# si4012_RTTY_01.net
KiCad netlist of a schematic drawn in EAGLE
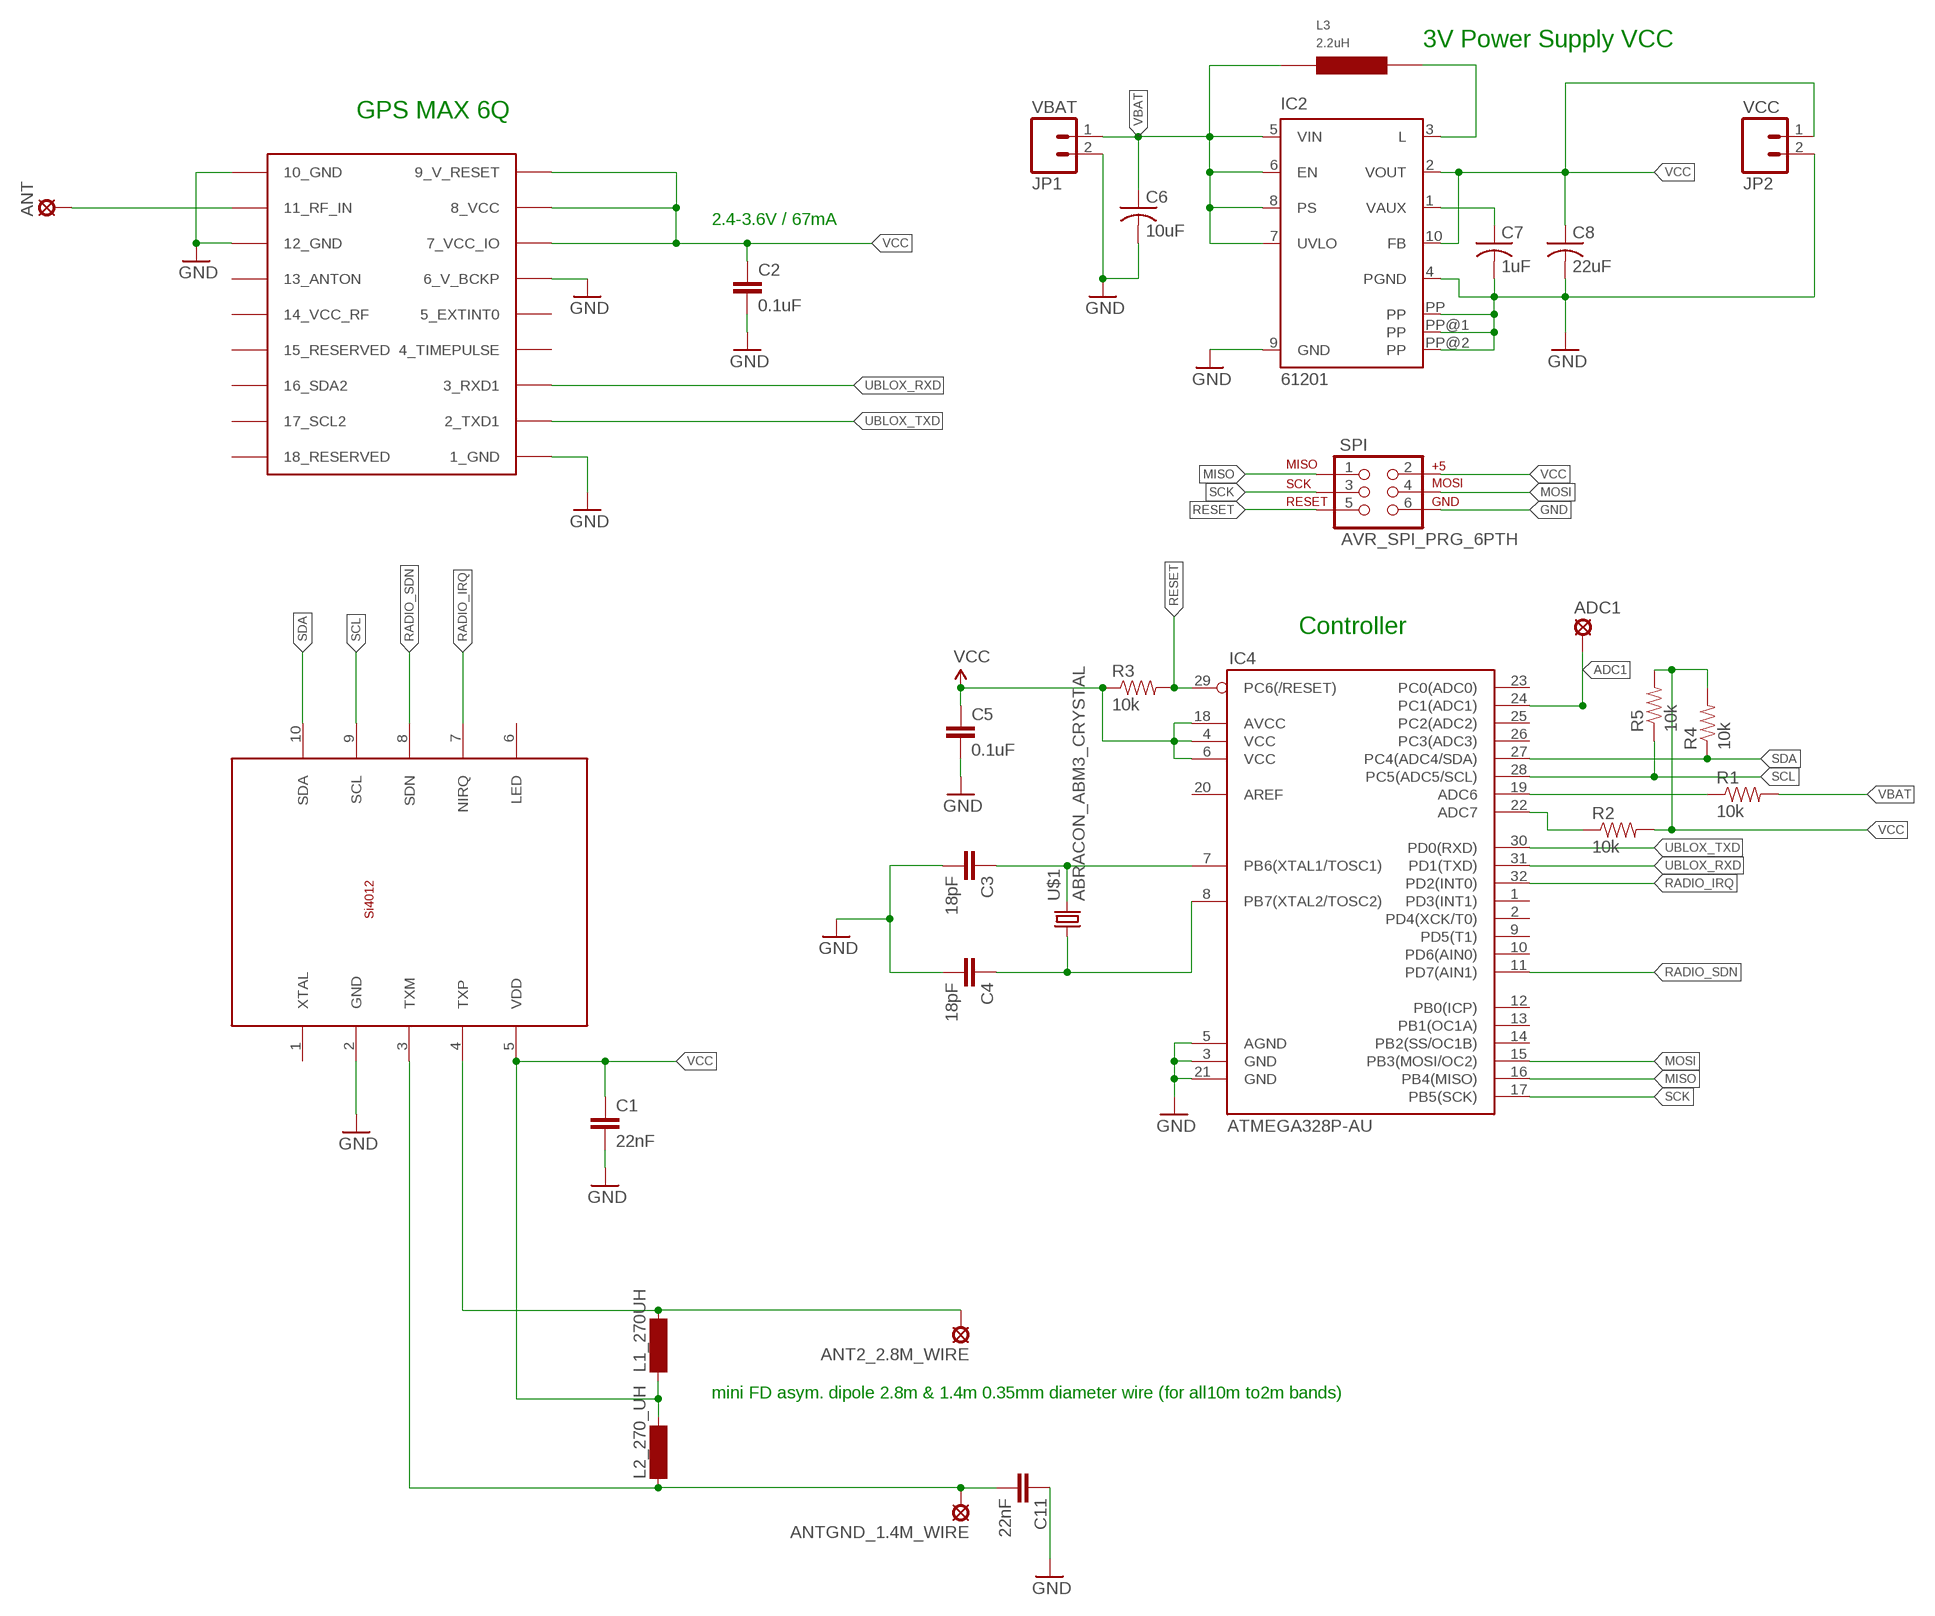
[diagram p0: schematic, sheet 1]

(export (version "E")
  (design (tool "Eeschema 10.0.6"))
  (components
    (comp (ref "ADC1")
      (value "LSP10")
      (footprint "eagle-import:LSP10")
      (libsource (lib "eagle-import") (part "LSP10"))
    )
    (comp (ref "ANT")
      (value "LSP10")
      (footprint "eagle-import:LSP10")
      (libsource (lib "eagle-import") (part "LSP10"))
    )
    (comp (ref "ANT2_2.8M_WIRE")
      (value "LSP10")
      (footprint "eagle-import:LSP10")
      (libsource (lib "eagle-import") (part "LSP10"))
    )
    (comp (ref "ANTGND_1.4M_WIRE")
      (value "LSP10")
      (footprint "eagle-import:LSP10")
      (libsource (lib "eagle-import") (part "LSP10"))
    )
    (comp (ref "C1")
      (value "22nF")
      (footprint "eagle-import:0402-CAP")
      (libsource (lib "eagle-import") (part "CAP0402-CAP"))
    )
    (comp (ref "C2")
      (value "0.1uF")
      (footprint "eagle-import:0402-CAP")
      (libsource (lib "eagle-import") (part "CAP0402-CAP"))
    )
    (comp (ref "C3")
      (value "18pF")
      (footprint "eagle-import:0402-CAP")
      (libsource (lib "eagle-import") (part "CAP0402-CAP"))
    )
    (comp (ref "C4")
      (value "18pF")
      (footprint "eagle-import:0402-CAP")
      (libsource (lib "eagle-import") (part "CAP0402-CAP"))
    )
    (comp (ref "C5")
      (value "0.1uF")
      (footprint "eagle-import:0402-CAP")
      (libsource (lib "eagle-import") (part "CAP0402-CAP"))
    )
    (comp (ref "C6")
      (value "10uF")
      (footprint "eagle-import:C1206")
      (libsource (lib "eagle-import") (part "C-USC1206"))
    )
    (comp (ref "C7")
      (value "1uF")
      (footprint "eagle-import:C1206")
      (libsource (lib "eagle-import") (part "C-USC1206"))
    )
    (comp (ref "C8")
      (value "22uF")
      (footprint "eagle-import:C1206")
      (libsource (lib "eagle-import") (part "C-USC1206"))
    )
    (comp (ref "C11")
      (value "22nF")
      (footprint "eagle-import:0402-CAP")
      (libsource (lib "eagle-import") (part "CAP0402-CAP"))
    )
    (comp (ref "IC2")
      (value "61201")
      (footprint "eagle-import:S-PDSO-N10")
      (fields (field (name "MPN") "TPS61201DRCT"))
      (libsource (lib "eagle-import") (part "TPS61201"))
    )
    (comp (ref "IC4")
      (value "ATMEGA328P-AU")
      (footprint "eagle-import:TQFP32-08")
      (libsource (lib "eagle-import") (part "ATMEGA168"))
    )
    (comp (ref "IC5")
      (value "UBLOX_MAX-6")
      (footprint "eagle-import:UBLOX_MAX-6")
      (libsource (lib "eagle-import") (part "UBLOX_MAX-6"))
    )
    (comp (ref "JP1")
      (value "VBAT")
      (footprint "eagle-import:1X02")
      (libsource (lib "eagle-import") (part "M02PTH"))
    )
    (comp (ref "JP2")
      (value "VCC")
      (footprint "eagle-import:1X02")
      (libsource (lib "eagle-import") (part "M02PTH"))
    )
    (comp (ref "L1_270UH")
      (value "SM-1206")
      (footprint "eagle-import:SM-1206")
      (libsource (lib "eagle-import") (part "SM-1206"))
    )
    (comp (ref "L2_270_UH")
      (value "SM-1206")
      (footprint "eagle-import:SM-1206")
      (libsource (lib "eagle-import") (part "SM-1206"))
    )
    (comp (ref "L3")
      (value "2.2uH")
      (footprint "eagle-import:LPS3015")
      (libsource (lib "eagle-import") (part "LPS3015"))
    )
    (comp (ref "R1")
      (value "10k")
      (footprint "eagle-import:0402-RES")
      (libsource (lib "eagle-import") (part "RESISTOR0402-RES"))
    )
    (comp (ref "R2")
      (value "10k")
      (footprint "eagle-import:0402-RES")
      (libsource (lib "eagle-import") (part "RESISTOR0402-RES"))
    )
    (comp (ref "R3")
      (value "10k")
      (footprint "eagle-import:0402-RES")
      (libsource (lib "eagle-import") (part "RESISTOR0402-RES"))
    )
    (comp (ref "R4")
      (value "10k")
      (footprint "eagle-import:0402-RES")
      (libsource (lib "eagle-import") (part "RESISTOR0402-RES"))
    )
    (comp (ref "R5")
      (value "10k")
      (footprint "eagle-import:0402-RES")
      (libsource (lib "eagle-import") (part "RESISTOR0402-RES"))
    )
    (comp (ref "SPI")
      (value "AVR_SPI_PRG_6PTH")
      (footprint "eagle-import:2X3")
      (libsource (lib "eagle-import") (part "AVR_SPI_PRG_6PTH"))
    )
    (comp (ref "U$1")
      (value "ABRACON_ABM3_CRYSTAL")
      (footprint "eagle-import:ABRACON_ABM3_CRYSTAL")
      (libsource (lib "eagle-import") (part "ABRACON_ABM3_CRYSTAL"))
    )
    (comp (ref "U$2")
      (value "SI4012")
      (footprint "eagle-import:MSOP_10")
      (libsource (lib "eagle-import") (part "SI4012"))
    )
  )
  (nets
    (net (code "1") (name "ADC1") (class "Default")
      (node (ref "ADC1") (pin "MP") (pinfunction "MP_MP") (pintype "passive"))
      (node (ref "IC4") (pin "24") (pinfunction "PC1(ADC1)_24") (pintype "bidirectional"))
    )
    (net (code "2") (name "GND") (class "Default")
      (node (ref "C1") (pin "2") (pinfunction "2_2") (pintype "passive"))
      (node (ref "C11") (pin "1") (pinfunction "1_1") (pintype "passive"))
      (node (ref "C2") (pin "2") (pinfunction "2_2") (pintype "passive"))
      (node (ref "C3") (pin "2") (pinfunction "2_2") (pintype "passive"))
      (node (ref "C4") (pin "2") (pinfunction "2_2") (pintype "passive"))
      (node (ref "C5") (pin "2") (pinfunction "2_2") (pintype "passive"))
      (node (ref "C6") (pin "2") (pinfunction "2_2") (pintype "passive"))
      (node (ref "C7") (pin "2") (pinfunction "2_2") (pintype "passive"))
      (node (ref "C8") (pin "2") (pinfunction "2_2") (pintype "passive"))
      (node (ref "IC2") (pin "4") (pinfunction "PGND_4") (pintype "power_in"))
      (node (ref "IC2") (pin "9") (pinfunction "GND_9") (pintype "power_in"))
      (node (ref "IC2") (pin "PP") (pinfunction "PP_PP") (pintype "power_in"))
      (node (ref "IC2") (pin "PP@1") (pinfunction "PP_PP@1") (pintype "power_in"))
      (node (ref "IC2") (pin "PP@2") (pinfunction "PP_PP@2") (pintype "power_in"))
      (node (ref "IC4") (pin "21") (pinfunction "GND_21") (pintype "bidirectional"))
      (node (ref "IC4") (pin "3") (pinfunction "GND_3") (pintype "bidirectional"))
      (node (ref "IC4") (pin "5") (pinfunction "AGND_5") (pintype "bidirectional"))
      (node (ref "IC5") (pin "10_GND") (pinfunction "10_GND_10_GND") (pintype "power_in"))
      (node (ref "IC5") (pin "12_GND") (pinfunction "12_GND_12_GND") (pintype "power_in"))
      (node (ref "IC5") (pin "1_GND") (pinfunction "1_GND_1_GND") (pintype "power_in"))
      (node (ref "IC5") (pin "6_V_BCKP") (pinfunction "6_V_BCKP_6_V_BCKP") (pintype "bidirectional"))
      (node (ref "JP1") (pin "2") (pinfunction "2_2") (pintype "passive"))
      (node (ref "JP2") (pin "2") (pinfunction "2_2") (pintype "passive"))
      (node (ref "SPI") (pin "6") (pinfunction "6_6") (pintype "passive"))
      (node (ref "U$2") (pin "2") (pinfunction "GND_2") (pintype "bidirectional"))
    )
    (net (code "3") (name "MISO") (class "Default")
      (node (ref "IC4") (pin "16") (pinfunction "PB4(MISO)_16") (pintype "bidirectional"))
      (node (ref "SPI") (pin "1") (pinfunction "1_1") (pintype "passive"))
    )
    (net (code "4") (name "MOSI") (class "Default")
      (node (ref "IC4") (pin "15") (pinfunction "PB3(MOSI/OC2)_15") (pintype "bidirectional"))
      (node (ref "SPI") (pin "4") (pinfunction "4_4") (pintype "passive"))
    )
    (net (code "5") (name "Net-(ANT-PadMP)") (class "Default")
      (node (ref "ANT") (pin "MP") (pinfunction "MP_MP") (pintype "passive"))
      (node (ref "IC5") (pin "11_RF_IN") (pinfunction "11_RF_IN_11_RF_IN") (pintype "bidirectional"))
    )
    (net (code "6") (name "Net-(IC2-L)") (class "Default")
      (node (ref "IC2") (pin "3") (pinfunction "L_3") (pintype "input"))
      (node (ref "L3") (pin "P$2") (pinfunction "2_P$2") (pintype "bidirectional"))
    )
    (net (code "7") (name "Net-(IC2-VAUX)") (class "Default")
      (node (ref "C7") (pin "1") (pinfunction "1_1") (pintype "passive"))
      (node (ref "IC2") (pin "1") (pinfunction "VAUX_1") (pintype "bidirectional"))
    )
    (net (code "8") (name "Net-(IC4-ADC6)") (class "Default")
      (node (ref "IC4") (pin "19") (pinfunction "ADC6_19") (pintype "bidirectional"))
      (node (ref "R1") (pin "1") (pinfunction "1_1") (pintype "passive"))
    )
    (net (code "9") (name "Net-(IC4-ADC7)") (class "Default")
      (node (ref "IC4") (pin "22") (pinfunction "ADC7_22") (pintype "bidirectional"))
      (node (ref "R2") (pin "1") (pinfunction "1_1") (pintype "passive"))
    )
    (net (code "10") (name "Net-(IC4-PB6(XTAL1{slash}TOSC1))") (class "Default")
      (node (ref "C3") (pin "1") (pinfunction "1_1") (pintype "passive"))
      (node (ref "IC4") (pin "7") (pinfunction "PB6(XTAL1/TOSC1)_7") (pintype "bidirectional"))
      (node (ref "U$1") (pin "P$2") (pinfunction "2_P$2") (pintype "passive"))
    )
    (net (code "11") (name "Net-(IC4-PB7(XTAL2{slash}TOSC2))") (class "Default")
      (node (ref "C4") (pin "1") (pinfunction "1_1") (pintype "passive"))
      (node (ref "IC4") (pin "8") (pinfunction "PB7(XTAL2/TOSC2)_8") (pintype "bidirectional"))
      (node (ref "U$1") (pin "P$1") (pinfunction "1_P$1") (pintype "passive"))
    )
    (net (code "12") (name "Net-(U$2-TXM)") (class "Default")
      (node (ref "ANTGND_1.4M_WIRE") (pin "MP") (pinfunction "MP_MP") (pintype "passive"))
      (node (ref "C11") (pin "2") (pinfunction "2_2") (pintype "passive"))
      (node (ref "L2_270_UH") (pin "1") (pinfunction "1_1") (pintype "passive"))
      (node (ref "U$2") (pin "3") (pinfunction "TXM_3") (pintype "bidirectional"))
    )
    (net (code "13") (name "Net-(U$2-TXP)") (class "Default")
      (node (ref "ANT2_2.8M_WIRE") (pin "MP") (pinfunction "MP_MP") (pintype "passive"))
      (node (ref "L1_270UH") (pin "2") (pinfunction "2_2") (pintype "passive"))
      (node (ref "U$2") (pin "4") (pinfunction "TXP_4") (pintype "bidirectional"))
    )
    (net (code "14") (name "RADIO_IRQ") (class "Default")
      (node (ref "IC4") (pin "32") (pinfunction "PD2(INT0)_32") (pintype "bidirectional"))
      (node (ref "U$2") (pin "7") (pinfunction "NIRQ_7") (pintype "bidirectional"))
    )
    (net (code "15") (name "RADIO_SDN") (class "Default")
      (node (ref "IC4") (pin "11") (pinfunction "PD7(AIN1)_11") (pintype "bidirectional"))
      (node (ref "U$2") (pin "8") (pinfunction "SDN_8") (pintype "bidirectional"))
    )
    (net (code "16") (name "RESET") (class "Default")
      (node (ref "IC4") (pin "29") (pinfunction "PC6(/RESET)_29") (pintype "bidirectional"))
      (node (ref "R3") (pin "2") (pinfunction "2_2") (pintype "passive"))
      (node (ref "SPI") (pin "5") (pinfunction "5_5") (pintype "passive"))
    )
    (net (code "17") (name "SCK") (class "Default")
      (node (ref "IC4") (pin "17") (pinfunction "PB5(SCK)_17") (pintype "bidirectional"))
      (node (ref "SPI") (pin "3") (pinfunction "3_3") (pintype "passive"))
    )
    (net (code "18") (name "SCL") (class "Default")
      (node (ref "IC4") (pin "28") (pinfunction "PC5(ADC5/SCL)_28") (pintype "bidirectional"))
      (node (ref "R5") (pin "1") (pinfunction "1_1") (pintype "passive"))
      (node (ref "U$2") (pin "9") (pinfunction "SCL_9") (pintype "bidirectional"))
    )
    (net (code "19") (name "SDA") (class "Default")
      (node (ref "IC4") (pin "27") (pinfunction "PC4(ADC4/SDA)_27") (pintype "bidirectional"))
      (node (ref "R4") (pin "1") (pinfunction "1_1") (pintype "passive"))
      (node (ref "U$2") (pin "10") (pinfunction "SDA_10") (pintype "bidirectional"))
    )
    (net (code "20") (name "UBLOX_RXD") (class "Default")
      (node (ref "IC4") (pin "31") (pinfunction "PD1(TXD)_31") (pintype "bidirectional"))
      (node (ref "IC5") (pin "3_RXD1") (pinfunction "3_RXD1_3_RXD1") (pintype "bidirectional"))
    )
    (net (code "21") (name "UBLOX_TXD") (class "Default")
      (node (ref "IC4") (pin "30") (pinfunction "PD0(RXD)_30") (pintype "bidirectional"))
      (node (ref "IC5") (pin "2_TXD1") (pinfunction "2_TXD1_2_TXD1") (pintype "bidirectional"))
    )
    (net (code "22") (name "VBAT") (class "Default")
      (node (ref "C6") (pin "1") (pinfunction "1_1") (pintype "passive"))
      (node (ref "IC2") (pin "5") (pinfunction "VIN_5") (pintype "input"))
      (node (ref "IC2") (pin "6") (pinfunction "EN_6") (pintype "input"))
      (node (ref "IC2") (pin "7") (pinfunction "UVLO_7") (pintype "input"))
      (node (ref "IC2") (pin "8") (pinfunction "PS_8") (pintype "input"))
      (node (ref "JP1") (pin "1") (pinfunction "1_1") (pintype "passive"))
      (node (ref "L3") (pin "P$1") (pinfunction "1_P$1") (pintype "bidirectional"))
      (node (ref "R1") (pin "2") (pinfunction "2_2") (pintype "passive"))
    )
    (net (code "23") (name "VCC") (class "Default")
      (node (ref "C1") (pin "1") (pinfunction "1_1") (pintype "passive"))
      (node (ref "C2") (pin "1") (pinfunction "1_1") (pintype "passive"))
      (node (ref "C5") (pin "1") (pinfunction "1_1") (pintype "passive"))
      (node (ref "C8") (pin "1") (pinfunction "1_1") (pintype "passive"))
      (node (ref "IC2") (pin "10") (pinfunction "FB_10") (pintype "input"))
      (node (ref "IC2") (pin "2") (pinfunction "VOUT_2") (pintype "passive"))
      (node (ref "IC4") (pin "18") (pinfunction "AVCC_18") (pintype "bidirectional"))
      (node (ref "IC4") (pin "4") (pinfunction "VCC_4") (pintype "bidirectional"))
      (node (ref "IC4") (pin "6") (pinfunction "VCC_6") (pintype "bidirectional"))
      (node (ref "IC5") (pin "7_VCC_IO") (pinfunction "7_VCC_IO_7_VCC_IO") (pintype "power_in"))
      (node (ref "IC5") (pin "8_VCC") (pinfunction "8_VCC_8_VCC") (pintype "power_in"))
      (node (ref "IC5") (pin "9_V_RESET") (pinfunction "9_V_RESET_9_V_RESET") (pintype "power_in"))
      (node (ref "JP2") (pin "1") (pinfunction "1_1") (pintype "passive"))
      (node (ref "L1_270UH") (pin "1") (pinfunction "1_1") (pintype "passive"))
      (node (ref "L2_270_UH") (pin "2") (pinfunction "2_2") (pintype "passive"))
      (node (ref "R2") (pin "2") (pinfunction "2_2") (pintype "passive"))
      (node (ref "R3") (pin "1") (pinfunction "1_1") (pintype "passive"))
      (node (ref "R4") (pin "2") (pinfunction "2_2") (pintype "passive"))
      (node (ref "R5") (pin "2") (pinfunction "2_2") (pintype "passive"))
      (node (ref "SPI") (pin "2") (pinfunction "2_2") (pintype "passive"))
      (node (ref "U$2") (pin "5") (pinfunction "VDD_5") (pintype "bidirectional"))
    )
    (net (code "24") (name "unconnected-(IC4-AREF-Pad20)") (class "Default")
      (node (ref "IC4") (pin "20") (pinfunction "AREF_20") (pintype "bidirectional"))
    )
    (net (code "25") (name "unconnected-(IC4-PB0(ICP)-Pad12)") (class "Default")
      (node (ref "IC4") (pin "12") (pinfunction "PB0(ICP)_12") (pintype "bidirectional"))
    )
    (net (code "26") (name "unconnected-(IC4-PB1(OC1A)-Pad13)") (class "Default")
      (node (ref "IC4") (pin "13") (pinfunction "PB1(OC1A)_13") (pintype "bidirectional"))
    )
    (net (code "27") (name "unconnected-(IC4-PB2(SS{slash}OC1B)-Pad14)") (class "Default")
      (node (ref "IC4") (pin "14") (pinfunction "PB2(SS/OC1B)_14") (pintype "bidirectional"))
    )
    (net (code "28") (name "unconnected-(IC4-PC0(ADC0)-Pad23)") (class "Default")
      (node (ref "IC4") (pin "23") (pinfunction "PC0(ADC0)_23") (pintype "bidirectional"))
    )
    (net (code "29") (name "unconnected-(IC4-PC2(ADC2)-Pad25)") (class "Default")
      (node (ref "IC4") (pin "25") (pinfunction "PC2(ADC2)_25") (pintype "bidirectional"))
    )
    (net (code "30") (name "unconnected-(IC4-PC3(ADC3)-Pad26)") (class "Default")
      (node (ref "IC4") (pin "26") (pinfunction "PC3(ADC3)_26") (pintype "bidirectional"))
    )
    (net (code "31") (name "unconnected-(IC4-PD3(INT1)-Pad1)") (class "Default")
      (node (ref "IC4") (pin "1") (pinfunction "PD3(INT1)_1") (pintype "bidirectional"))
    )
    (net (code "32") (name "unconnected-(IC4-PD4(XCK{slash}T0)-Pad2)") (class "Default")
      (node (ref "IC4") (pin "2") (pinfunction "PD4(XCK/T0)_2") (pintype "bidirectional"))
    )
    (net (code "33") (name "unconnected-(IC4-PD5(T1)-Pad9)") (class "Default")
      (node (ref "IC4") (pin "9") (pinfunction "PD5(T1)_9") (pintype "bidirectional"))
    )
    (net (code "34") (name "unconnected-(IC4-PD6(AIN0)-Pad10)") (class "Default")
      (node (ref "IC4") (pin "10") (pinfunction "PD6(AIN0)_10") (pintype "bidirectional"))
    )
    (net (code "35") (name "unconnected-(IC5-Pad4_TIMEPULSE)") (class "Default")
      (node (ref "IC5") (pin "4_TIMEPULSE") (pinfunction "4_TIMEPULSE_4_TIMEPULSE") (pintype "bidirectional"))
    )
    (net (code "36") (name "unconnected-(IC5-Pad5_EXTINT0)") (class "Default")
      (node (ref "IC5") (pin "5_EXTINT0") (pinfunction "5_EXTINT0_5_EXTINT0") (pintype "bidirectional"))
    )
    (net (code "37") (name "unconnected-(IC5-Pad13_ANTON)") (class "Default")
      (node (ref "IC5") (pin "13_ANTON") (pinfunction "13_ANTON_13_ANTON") (pintype "bidirectional"))
    )
    (net (code "38") (name "unconnected-(IC5-Pad14_VCC_RF)") (class "Default")
      (node (ref "IC5") (pin "14_VCC_RF") (pinfunction "14_VCC_RF_14_VCC_RF") (pintype "bidirectional"))
    )
    (net (code "39") (name "unconnected-(IC5-Pad15_RESERVED)") (class "Default")
      (node (ref "IC5") (pin "15_RESERVED") (pinfunction "15_RESERVED_15_RESERVED") (pintype "bidirectional"))
    )
    (net (code "40") (name "unconnected-(IC5-Pad16_SDA2)") (class "Default")
      (node (ref "IC5") (pin "16_SDA2") (pinfunction "16_SDA2_16_SDA2") (pintype "bidirectional"))
    )
    (net (code "41") (name "unconnected-(IC5-Pad17_SCL2)") (class "Default")
      (node (ref "IC5") (pin "17_SCL2") (pinfunction "17_SCL2_17_SCL2") (pintype "bidirectional"))
    )
    (net (code "42") (name "unconnected-(IC5-Pad18_RESERVED)") (class "Default")
      (node (ref "IC5") (pin "18_RESERVED") (pinfunction "18_RESERVED_18_RESERVED") (pintype "bidirectional"))
    )
    (net (code "43") (name "unconnected-(U$2-LED-Pad6)") (class "Default")
      (node (ref "U$2") (pin "6") (pinfunction "LED_6") (pintype "bidirectional"))
    )
    (net (code "44") (name "unconnected-(U$2-XTAL-Pad1)") (class "Default")
      (node (ref "U$2") (pin "1") (pinfunction "XTAL_1") (pintype "bidirectional"))
    )
  )
)
